# M207E.net
KiCad netlist of a schematic drawn in EAGLE
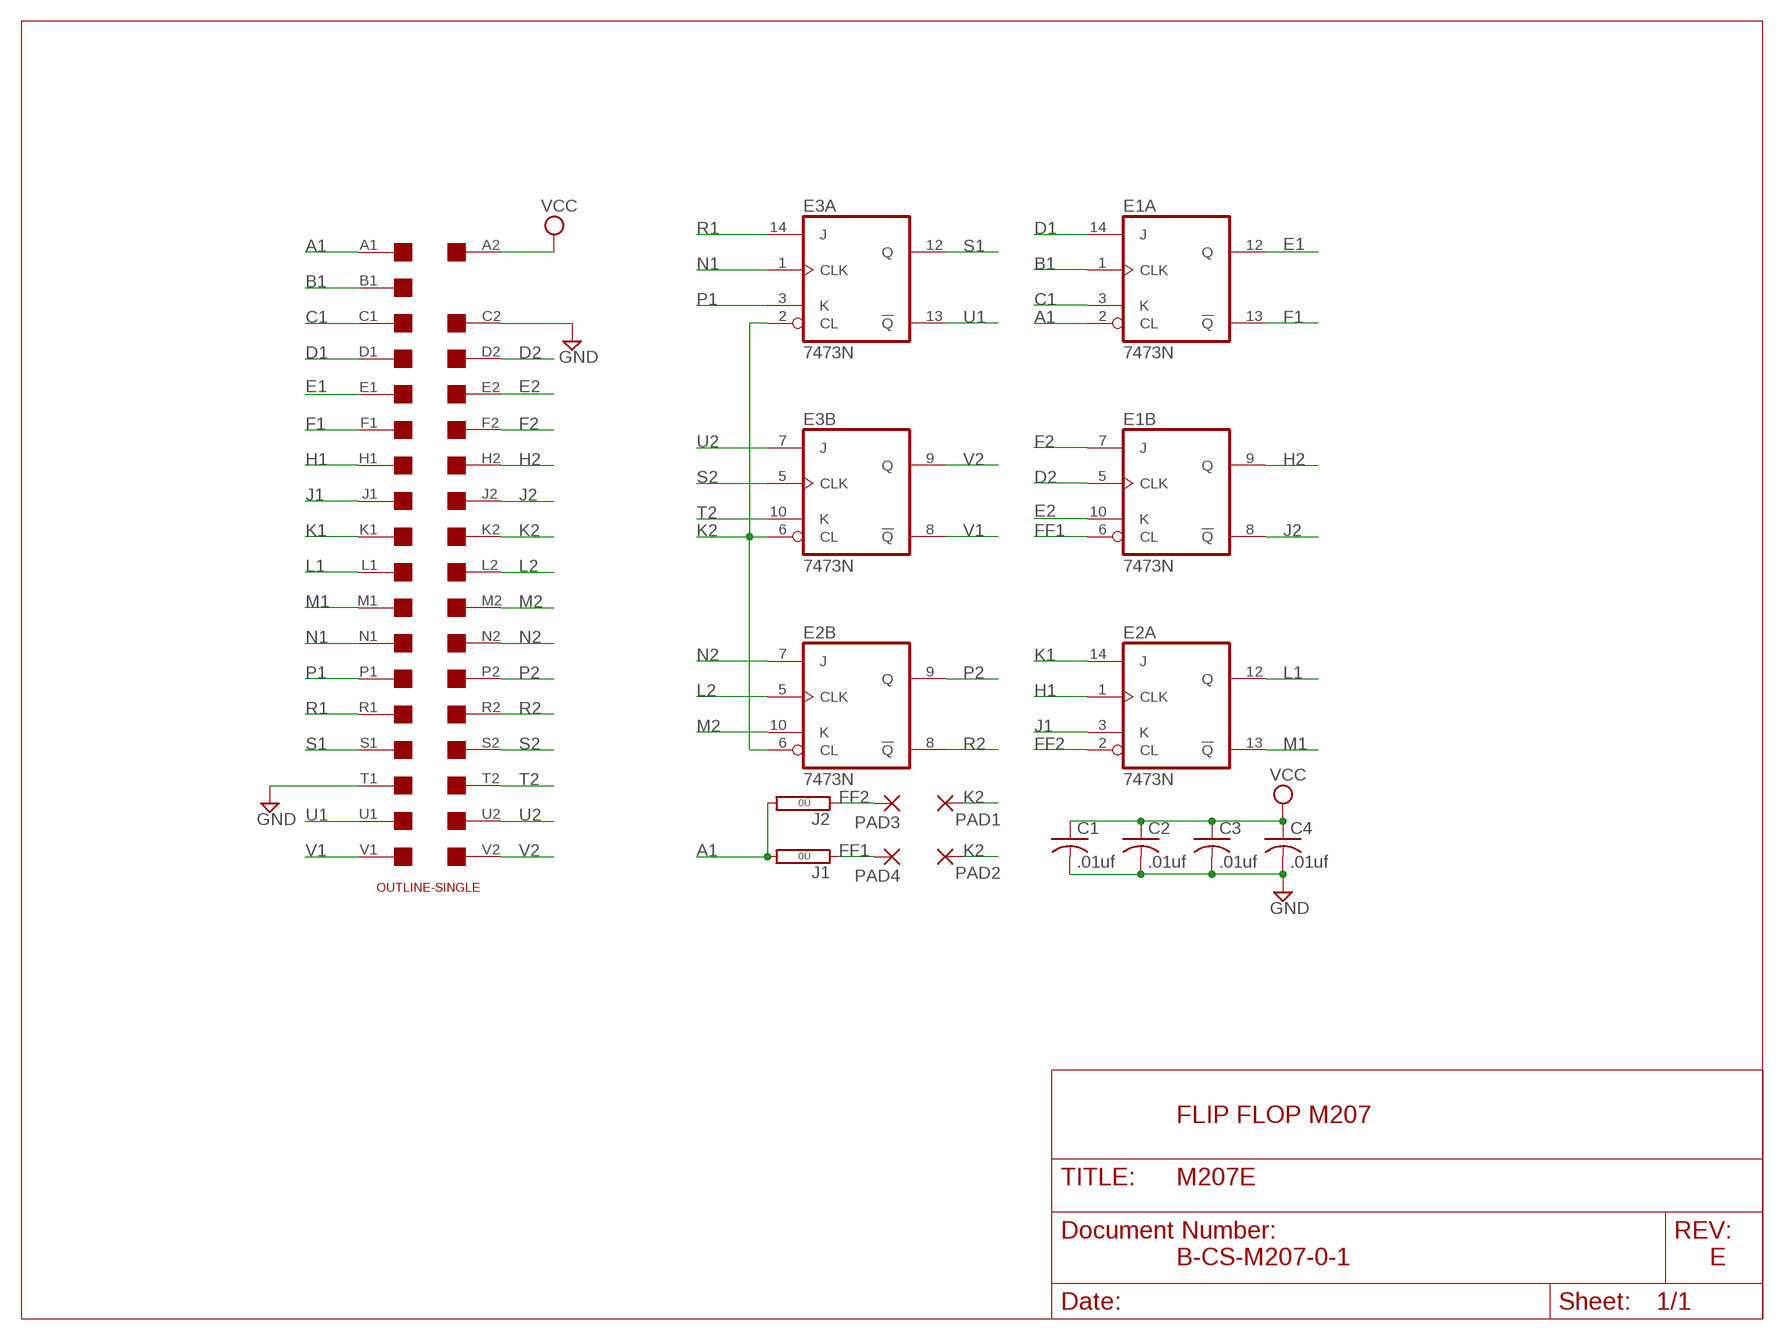
[diagram p0: schematic, sheet 1]

(export (version "E")
  (design (tool "Eeschema 10.0.6"))
  (components
    (comp (ref "C1")
      (value ".01uf")
      (footprint "eagle-import:C050-025X075")
      (libsource (lib "eagle-import") (part "C-US050-025X075"))
    )
    (comp (ref "C2")
      (value ".01uf")
      (footprint "eagle-import:C050-025X075")
      (libsource (lib "eagle-import") (part "C-US050-025X075"))
    )
    (comp (ref "C3")
      (value ".01uf")
      (footprint "eagle-import:C050-025X075")
      (libsource (lib "eagle-import") (part "C-US050-025X075"))
    )
    (comp (ref "C4")
      (value ".01uf")
      (footprint "eagle-import:C050-025X075")
      (libsource (lib "eagle-import") (part "C-US050-025X075"))
    )
    (comp (ref "E1")
      (value "7473N")
      (footprint "eagle-import:DIL14")
      (libsource (lib "eagle-import") (part "7473NLS"))
    )
    (comp (ref "E2")
      (value "7473N")
      (footprint "eagle-import:DIL14")
      (libsource (lib "eagle-import") (part "7473NLS"))
    )
    (comp (ref "E3")
      (value "7473N")
      (footprint "eagle-import:DIL14")
      (libsource (lib "eagle-import") (part "7473NLS"))
    )
    (comp (ref "J1")
      (value "0R")
      (footprint "eagle-import:0R_10")
      (libsource (lib "eagle-import") (part "0R"))
    )
    (comp (ref "J2")
      (value "0R")
      (footprint "eagle-import:0R_10")
      (libsource (lib "eagle-import") (part "0R"))
    )
    (comp (ref "PAD1")
      (value "1,6/0,8")
      (footprint "eagle-import:1,6_0,8")
      (libsource (lib "eagle-import") (part "1,6/0,8"))
    )
    (comp (ref "PAD2")
      (value "1,6/0,8")
      (footprint "eagle-import:1,6_0,8")
      (libsource (lib "eagle-import") (part "1,6/0,8"))
    )
    (comp (ref "PAD3")
      (value "1,6/0,8")
      (footprint "eagle-import:1,6_0,8")
      (libsource (lib "eagle-import") (part "1,6/0,8"))
    )
    (comp (ref "PAD4")
      (value "1,6/0,8")
      (footprint "eagle-import:1,6_0,8")
      (libsource (lib "eagle-import") (part "1,6/0,8"))
    )
    (comp (ref "U$1")
      (value "SINGLE")
      (footprint "eagle-import:EDGE-CON2")
      (libsource (lib "eagle-import") (part "SINGLE"))
    )
    (comp (ref "U$4")
      (value "OUTLINE-SINGLE")
      (footprint "eagle-import:SINGLE")
      (libsource (lib "eagle-import") (part "OUTLINE-SINGLE"))
    )
  )
  (nets
    (net (code "1") (name "/A1") (class "Default")
      (node (ref "E1") (pin "2") (pinfunction "CL_2") (pintype "input"))
      (node (ref "J1") (pin "2") (pinfunction "2_2") (pintype "passive"))
      (node (ref "J2") (pin "2") (pinfunction "2_2") (pintype "passive"))
      (node (ref "U$1") (pin "A1") (pinfunction "1_A1") (pintype "bidirectional"))
    )
    (net (code "2") (name "/B1") (class "Default")
      (node (ref "E1") (pin "1") (pinfunction "CLK_1") (pintype "input"))
      (node (ref "U$1") (pin "B1") (pinfunction "1_B1") (pintype "bidirectional"))
    )
    (net (code "3") (name "/C1") (class "Default")
      (node (ref "E1") (pin "3") (pinfunction "K_3") (pintype "input"))
      (node (ref "U$1") (pin "C1") (pinfunction "1_C1") (pintype "bidirectional"))
    )
    (net (code "4") (name "/D1") (class "Default")
      (node (ref "E1") (pin "14") (pinfunction "J_14") (pintype "input"))
      (node (ref "U$1") (pin "D1") (pinfunction "1_D1") (pintype "bidirectional"))
    )
    (net (code "5") (name "/D2") (class "Default")
      (node (ref "E1") (pin "5") (pinfunction "CLK_5") (pintype "input"))
      (node (ref "U$1") (pin "D2") (pinfunction "1_D2") (pintype "bidirectional"))
    )
    (net (code "6") (name "/E1") (class "Default")
      (node (ref "E1") (pin "12") (pinfunction "Q_12") (pintype "output"))
      (node (ref "U$1") (pin "E1") (pinfunction "1_E1") (pintype "bidirectional"))
    )
    (net (code "7") (name "/E2") (class "Default")
      (node (ref "E1") (pin "10") (pinfunction "K_10") (pintype "input"))
      (node (ref "U$1") (pin "E2") (pinfunction "1_E2") (pintype "bidirectional"))
    )
    (net (code "8") (name "/F1") (class "Default")
      (node (ref "E1") (pin "13") (pinfunction "~{Q}_13") (pintype "output"))
      (node (ref "U$1") (pin "F1") (pinfunction "1_F1") (pintype "bidirectional"))
    )
    (net (code "9") (name "/F2") (class "Default")
      (node (ref "E1") (pin "7") (pinfunction "J_7") (pintype "input"))
      (node (ref "U$1") (pin "F2") (pinfunction "1_F2") (pintype "bidirectional"))
    )
    (net (code "10") (name "/FF1") (class "Default")
      (node (ref "E1") (pin "6") (pinfunction "CL_6") (pintype "input"))
      (node (ref "J1") (pin "1") (pinfunction "1_1") (pintype "passive"))
      (node (ref "PAD4") (pin "1") (pinfunction "P_1") (pintype "passive"))
    )
    (net (code "11") (name "/FF2") (class "Default")
      (node (ref "E2") (pin "2") (pinfunction "CL_2") (pintype "input"))
      (node (ref "J2") (pin "1") (pinfunction "1_1") (pintype "passive"))
      (node (ref "PAD3") (pin "1") (pinfunction "P_1") (pintype "passive"))
    )
    (net (code "12") (name "/H1") (class "Default")
      (node (ref "E2") (pin "1") (pinfunction "CLK_1") (pintype "input"))
      (node (ref "U$1") (pin "H1") (pinfunction "1_H1") (pintype "bidirectional"))
    )
    (net (code "13") (name "/H2") (class "Default")
      (node (ref "E1") (pin "9") (pinfunction "Q_9") (pintype "output"))
      (node (ref "U$1") (pin "H2") (pinfunction "1_H2") (pintype "bidirectional"))
    )
    (net (code "14") (name "/J1") (class "Default")
      (node (ref "E2") (pin "3") (pinfunction "K_3") (pintype "input"))
      (node (ref "U$1") (pin "J1") (pinfunction "1_J1") (pintype "bidirectional"))
    )
    (net (code "15") (name "/J2") (class "Default")
      (node (ref "E1") (pin "8") (pinfunction "~{Q}_8") (pintype "output"))
      (node (ref "U$1") (pin "J2") (pinfunction "1_J2") (pintype "bidirectional"))
    )
    (net (code "16") (name "/K1") (class "Default")
      (node (ref "E2") (pin "14") (pinfunction "J_14") (pintype "input"))
      (node (ref "U$1") (pin "K1") (pinfunction "1_K1") (pintype "bidirectional"))
    )
    (net (code "17") (name "/K2") (class "Default")
      (node (ref "E2") (pin "6") (pinfunction "CL_6") (pintype "input"))
      (node (ref "E3") (pin "2") (pinfunction "CL_2") (pintype "input"))
      (node (ref "E3") (pin "6") (pinfunction "CL_6") (pintype "input"))
      (node (ref "PAD1") (pin "1") (pinfunction "P_1") (pintype "passive"))
      (node (ref "PAD2") (pin "1") (pinfunction "P_1") (pintype "passive"))
      (node (ref "U$1") (pin "K2") (pinfunction "1_K2") (pintype "bidirectional"))
    )
    (net (code "18") (name "/L1") (class "Default")
      (node (ref "E2") (pin "12") (pinfunction "Q_12") (pintype "output"))
      (node (ref "U$1") (pin "L1") (pinfunction "1_L1") (pintype "bidirectional"))
    )
    (net (code "19") (name "/L2") (class "Default")
      (node (ref "E2") (pin "5") (pinfunction "CLK_5") (pintype "input"))
      (node (ref "U$1") (pin "L2") (pinfunction "1_L2") (pintype "bidirectional"))
    )
    (net (code "20") (name "/M1") (class "Default")
      (node (ref "E2") (pin "13") (pinfunction "~{Q}_13") (pintype "output"))
      (node (ref "U$1") (pin "M1") (pinfunction "1_M1") (pintype "bidirectional"))
    )
    (net (code "21") (name "/M2") (class "Default")
      (node (ref "E2") (pin "10") (pinfunction "K_10") (pintype "input"))
      (node (ref "U$1") (pin "M2") (pinfunction "1_M2") (pintype "bidirectional"))
    )
    (net (code "22") (name "/N1") (class "Default")
      (node (ref "E3") (pin "1") (pinfunction "CLK_1") (pintype "input"))
      (node (ref "U$1") (pin "N1") (pinfunction "1_N1") (pintype "bidirectional"))
    )
    (net (code "23") (name "/N2") (class "Default")
      (node (ref "E2") (pin "7") (pinfunction "J_7") (pintype "input"))
      (node (ref "U$1") (pin "N2") (pinfunction "1_N2") (pintype "bidirectional"))
    )
    (net (code "24") (name "/P1") (class "Default")
      (node (ref "E3") (pin "3") (pinfunction "K_3") (pintype "input"))
      (node (ref "U$1") (pin "P1") (pinfunction "1_P1") (pintype "bidirectional"))
    )
    (net (code "25") (name "/P2") (class "Default")
      (node (ref "E2") (pin "9") (pinfunction "Q_9") (pintype "output"))
      (node (ref "U$1") (pin "P2") (pinfunction "1_P2") (pintype "bidirectional"))
    )
    (net (code "26") (name "/R1") (class "Default")
      (node (ref "E3") (pin "14") (pinfunction "J_14") (pintype "input"))
      (node (ref "U$1") (pin "R1") (pinfunction "1_R1") (pintype "bidirectional"))
    )
    (net (code "27") (name "/R2") (class "Default")
      (node (ref "E2") (pin "8") (pinfunction "~{Q}_8") (pintype "output"))
      (node (ref "U$1") (pin "R2") (pinfunction "1_R2") (pintype "bidirectional"))
    )
    (net (code "28") (name "/S1") (class "Default")
      (node (ref "E3") (pin "12") (pinfunction "Q_12") (pintype "output"))
      (node (ref "U$1") (pin "S1") (pinfunction "1_S1") (pintype "bidirectional"))
    )
    (net (code "29") (name "/S2") (class "Default")
      (node (ref "E3") (pin "5") (pinfunction "CLK_5") (pintype "input"))
      (node (ref "U$1") (pin "S2") (pinfunction "1_S2") (pintype "bidirectional"))
    )
    (net (code "30") (name "/T2") (class "Default")
      (node (ref "E3") (pin "10") (pinfunction "K_10") (pintype "input"))
      (node (ref "U$1") (pin "T2") (pinfunction "1_T2") (pintype "bidirectional"))
    )
    (net (code "31") (name "/U1") (class "Default")
      (node (ref "E3") (pin "13") (pinfunction "~{Q}_13") (pintype "output"))
      (node (ref "U$1") (pin "U1") (pinfunction "1_U1") (pintype "bidirectional"))
    )
    (net (code "32") (name "/U2") (class "Default")
      (node (ref "E3") (pin "7") (pinfunction "J_7") (pintype "input"))
      (node (ref "U$1") (pin "U2") (pinfunction "1_U2") (pintype "bidirectional"))
    )
    (net (code "33") (name "/V1") (class "Default")
      (node (ref "E3") (pin "8") (pinfunction "~{Q}_8") (pintype "output"))
      (node (ref "U$1") (pin "V1") (pinfunction "1_V1") (pintype "bidirectional"))
    )
    (net (code "34") (name "/V2") (class "Default")
      (node (ref "E3") (pin "9") (pinfunction "Q_9") (pintype "output"))
      (node (ref "U$1") (pin "V2") (pinfunction "1_V2") (pintype "bidirectional"))
    )
    (net (code "35") (name "GND") (class "Default")
      (node (ref "C1") (pin "2") (pinfunction "2_2") (pintype "passive"))
      (node (ref "C2") (pin "2") (pinfunction "2_2") (pintype "passive"))
      (node (ref "C3") (pin "2") (pinfunction "2_2") (pintype "passive"))
      (node (ref "C4") (pin "2") (pinfunction "2_2") (pintype "passive"))
      (node (ref "U$1") (pin "C2") (pinfunction "1_C2") (pintype "bidirectional"))
      (node (ref "U$1") (pin "T1") (pinfunction "1_T1") (pintype "bidirectional"))
    )
    (net (code "36") (name "VCC") (class "Default")
      (node (ref "C1") (pin "1") (pinfunction "1_1") (pintype "passive"))
      (node (ref "C2") (pin "1") (pinfunction "1_1") (pintype "passive"))
      (node (ref "C3") (pin "1") (pinfunction "1_1") (pintype "passive"))
      (node (ref "C4") (pin "1") (pinfunction "1_1") (pintype "passive"))
      (node (ref "U$1") (pin "A2") (pinfunction "1_A2") (pintype "bidirectional"))
    )
  )
)
